# TPS62827_3_3V_Buck_Converter.net
KiCad netlist of a schematic drawn in EAGLE
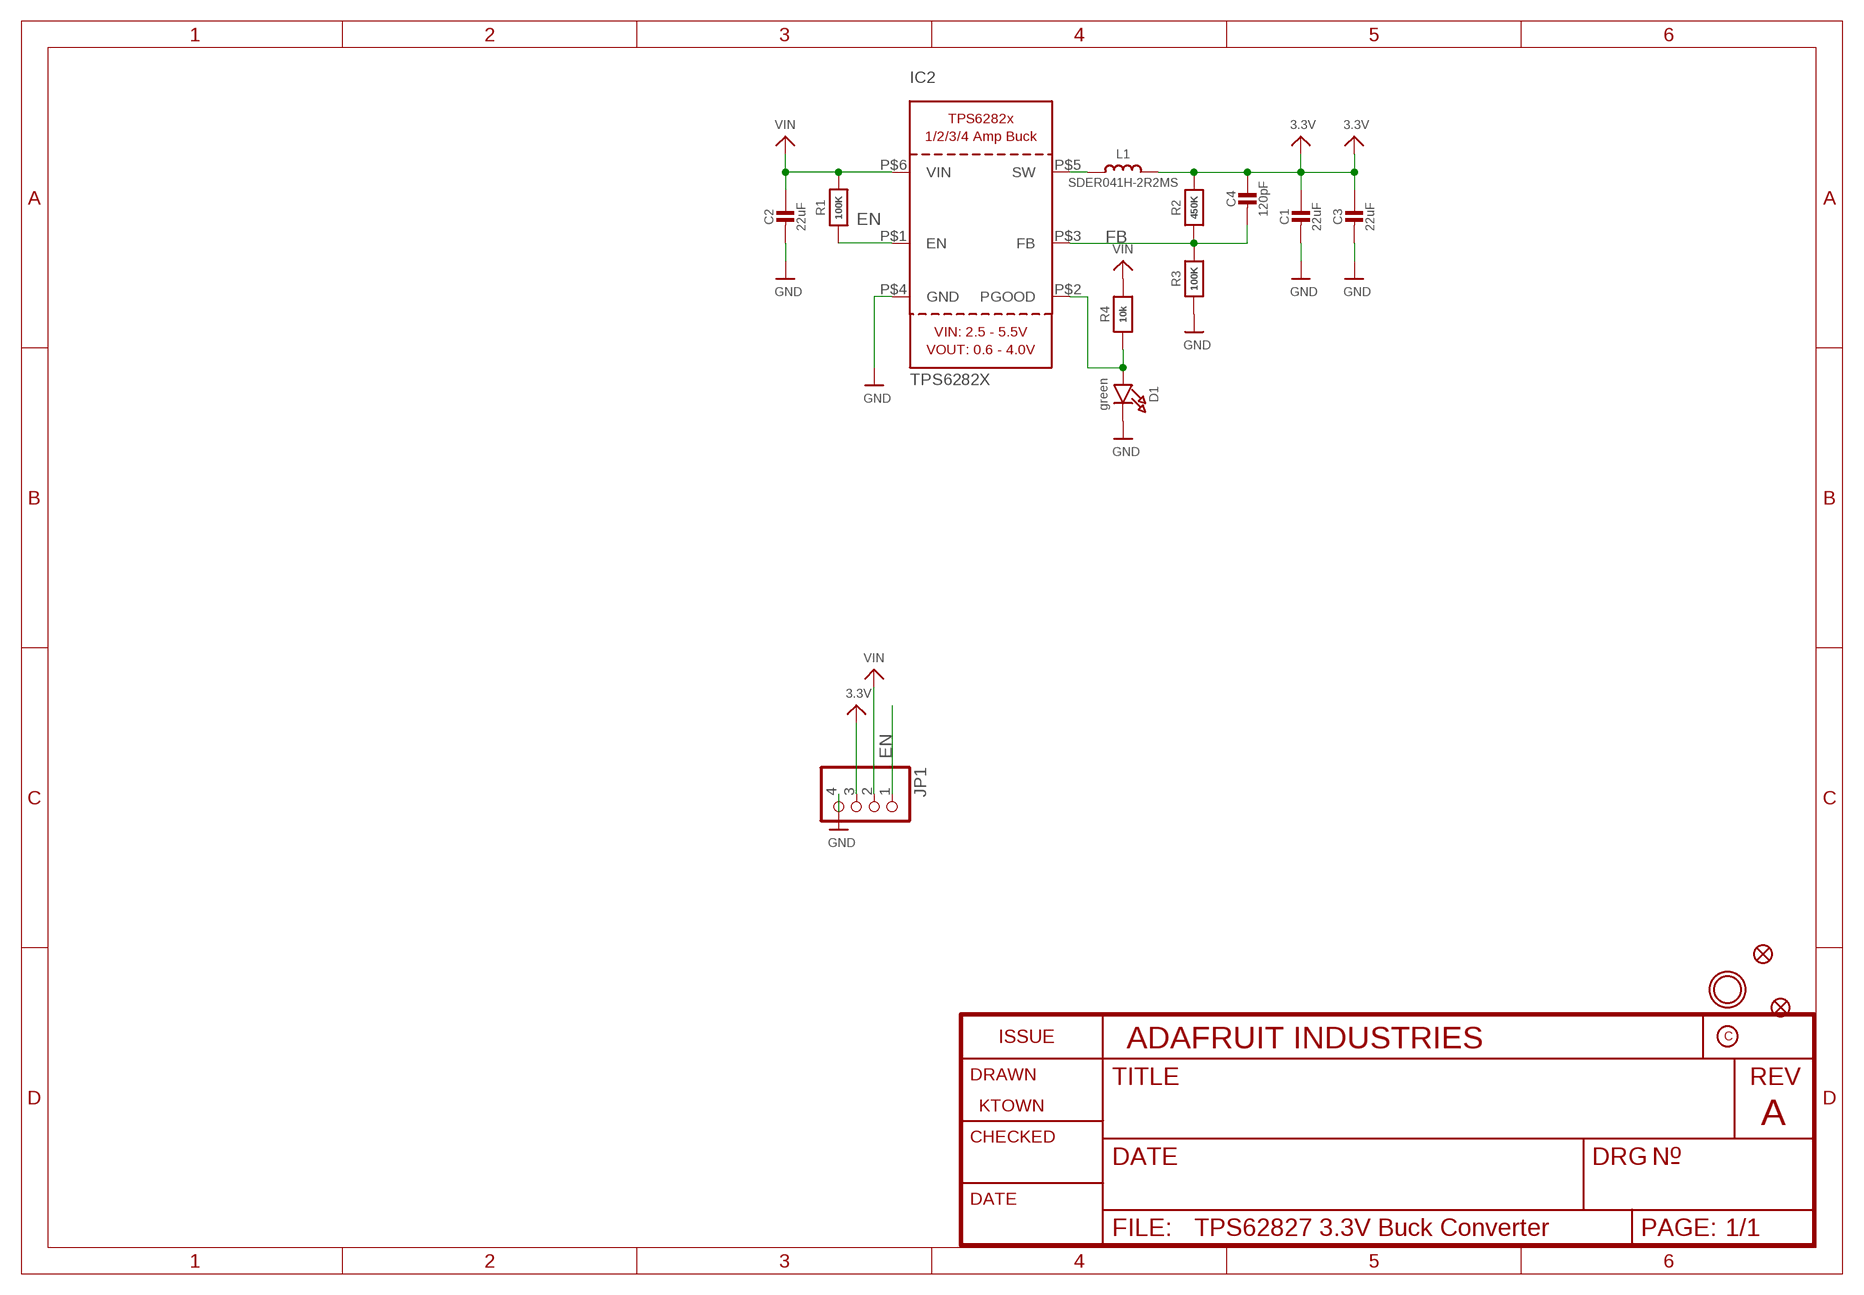
[diagram p0: schematic, sheet 1]

(export (version "E")
  (design (tool "Eeschema 10.0.6"))
  (components
    (comp (ref "C1")
      (value "22uF")
      (footprint "eagle-import:0805-NO")
      (libsource (lib "eagle-import") (part "CAP_CERAMIC0805-NOOUTLINE"))
    )
    (comp (ref "C2")
      (value "22uF")
      (footprint "eagle-import:0805-NO")
      (libsource (lib "eagle-import") (part "CAP_CERAMIC0805-NOOUTLINE"))
    )
    (comp (ref "C3")
      (value "22uF")
      (footprint "eagle-import:0805-NO")
      (libsource (lib "eagle-import") (part "CAP_CERAMIC0805-NOOUTLINE"))
    )
    (comp (ref "C4")
      (value "120pF")
      (footprint "eagle-import:0603-NO")
      (libsource (lib "eagle-import") (part "CAP_CERAMIC0603_NO"))
    )
    (comp (ref "D1")
      (value "green")
      (footprint "eagle-import:CHIPLED_0603_NOOUTLINE")
      (libsource (lib "eagle-import") (part "LED0603_NOOUTLINE"))
    )
    (comp (ref "FID1")
      (value "FIDUCIAL_1MM")
      (footprint "eagle-import:FIDUCIAL_1MM")
      (libsource (lib "eagle-import") (part "FIDUCIAL_1MM"))
    )
    (comp (ref "FID2")
      (value "FIDUCIAL_1MM")
      (footprint "eagle-import:FIDUCIAL_1MM")
      (libsource (lib "eagle-import") (part "FIDUCIAL_1MM"))
    )
    (comp (ref "IC2")
      (value "TPS6282X")
      (footprint "eagle-import:VSON_6")
      (libsource (lib "eagle-import") (part "TPS6282X"))
    )
    (comp (ref "JP1")
      (value "HEADER-1X4ROUND")
      (footprint "eagle-import:1X04_ROUND")
      (libsource (lib "eagle-import") (part "HEADER-1X4ROUND"))
    )
    (comp (ref "L1")
      (value "SDER041H-2R2MS")
      (footprint "eagle-import:INDUCTOR_4X4MM_SRP0415")
      (libsource (lib "eagle-import") (part "INDUCTOR_SRP0415"))
    )
    (comp (ref "R1")
      (value "100K")
      (footprint "eagle-import:0603-NO")
      (libsource (lib "eagle-import") (part "RESISTOR_0603_NOOUT"))
    )
    (comp (ref "R2")
      (value "450K")
      (footprint "eagle-import:0603-NO")
      (libsource (lib "eagle-import") (part "RESISTOR_0603_NOOUT"))
    )
    (comp (ref "R3")
      (value "100K")
      (footprint "eagle-import:0603-NO")
      (libsource (lib "eagle-import") (part "RESISTOR_0603_NOOUT"))
    )
    (comp (ref "R4")
      (value "10k")
      (footprint "eagle-import:_0603MP")
      (libsource (lib "eagle-import") (part "RESISTOR_0603MP"))
    )
    (comp (ref "U$9")
      (value "MOUNTINGHOLE2.5")
      (footprint "eagle-import:MOUNTINGHOLE_2.5_PLATED")
      (libsource (lib "eagle-import") (part "MOUNTINGHOLE2.5"))
    )
  )
  (nets
    (net (code "1") (name "/EN") (class "Default")
      (node (ref "IC2") (pin "P$1") (pinfunction "EN_P$1") (pintype "input"))
      (node (ref "JP1") (pin "1") (pinfunction "1_1") (pintype "passive"))
      (node (ref "R1") (pin "2") (pinfunction "2_2") (pintype "passive"))
    )
    (net (code "2") (name "/FB") (class "Default")
      (node (ref "C4") (pin "2") (pinfunction "2_2") (pintype "passive"))
      (node (ref "IC2") (pin "P$3") (pinfunction "FB_P$3") (pintype "input"))
      (node (ref "R2") (pin "1") (pinfunction "1_1") (pintype "passive"))
      (node (ref "R3") (pin "2") (pinfunction "2_2") (pintype "passive"))
    )
    (net (code "3") (name "3.3V") (class "Default")
      (node (ref "C1") (pin "1") (pinfunction "1_1") (pintype "passive"))
      (node (ref "C3") (pin "1") (pinfunction "1_1") (pintype "passive"))
      (node (ref "C4") (pin "1") (pinfunction "1_1") (pintype "passive"))
      (node (ref "JP1") (pin "3") (pinfunction "3_3") (pintype "passive"))
      (node (ref "L1") (pin "P$2") (pinfunction "2_P$2") (pintype "passive"))
      (node (ref "R2") (pin "2") (pinfunction "2_2") (pintype "passive"))
    )
    (net (code "4") (name "GND") (class "Default")
      (node (ref "C1") (pin "2") (pinfunction "2_2") (pintype "passive"))
      (node (ref "C2") (pin "2") (pinfunction "2_2") (pintype "passive"))
      (node (ref "C3") (pin "2") (pinfunction "2_2") (pintype "passive"))
      (node (ref "D1") (pin "C") (pinfunction "C_C") (pintype "passive"))
      (node (ref "IC2") (pin "P$4") (pinfunction "GND_P$4") (pintype "power_in"))
      (node (ref "JP1") (pin "4") (pinfunction "4_4") (pintype "passive"))
      (node (ref "R3") (pin "1") (pinfunction "1_1") (pintype "passive"))
    )
    (net (code "5") (name "Net-(IC2-PGOOD)") (class "Default")
      (node (ref "D1") (pin "A") (pinfunction "A_A") (pintype "passive"))
      (node (ref "IC2") (pin "P$2") (pinfunction "PGOOD_P$2") (pintype "output"))
      (node (ref "R4") (pin "1") (pinfunction "1_1") (pintype "passive"))
    )
    (net (code "6") (name "Net-(IC2-SW)") (class "Default")
      (node (ref "IC2") (pin "P$5") (pinfunction "SW_P$5") (pintype "power_in"))
      (node (ref "L1") (pin "P$1") (pinfunction "1_P$1") (pintype "passive"))
    )
    (net (code "7") (name "VIN") (class "Default")
      (node (ref "C2") (pin "1") (pinfunction "1_1") (pintype "passive"))
      (node (ref "IC2") (pin "P$6") (pinfunction "VIN_P$6") (pintype "power_in"))
      (node (ref "JP1") (pin "2") (pinfunction "2_2") (pintype "passive"))
      (node (ref "R1") (pin "1") (pinfunction "1_1") (pintype "passive"))
      (node (ref "R4") (pin "2") (pinfunction "2_2") (pintype "passive"))
    )
  )
)
